# Reflow-controller-ESP32.net
KiCad netlist of a schematic drawn in EAGLE
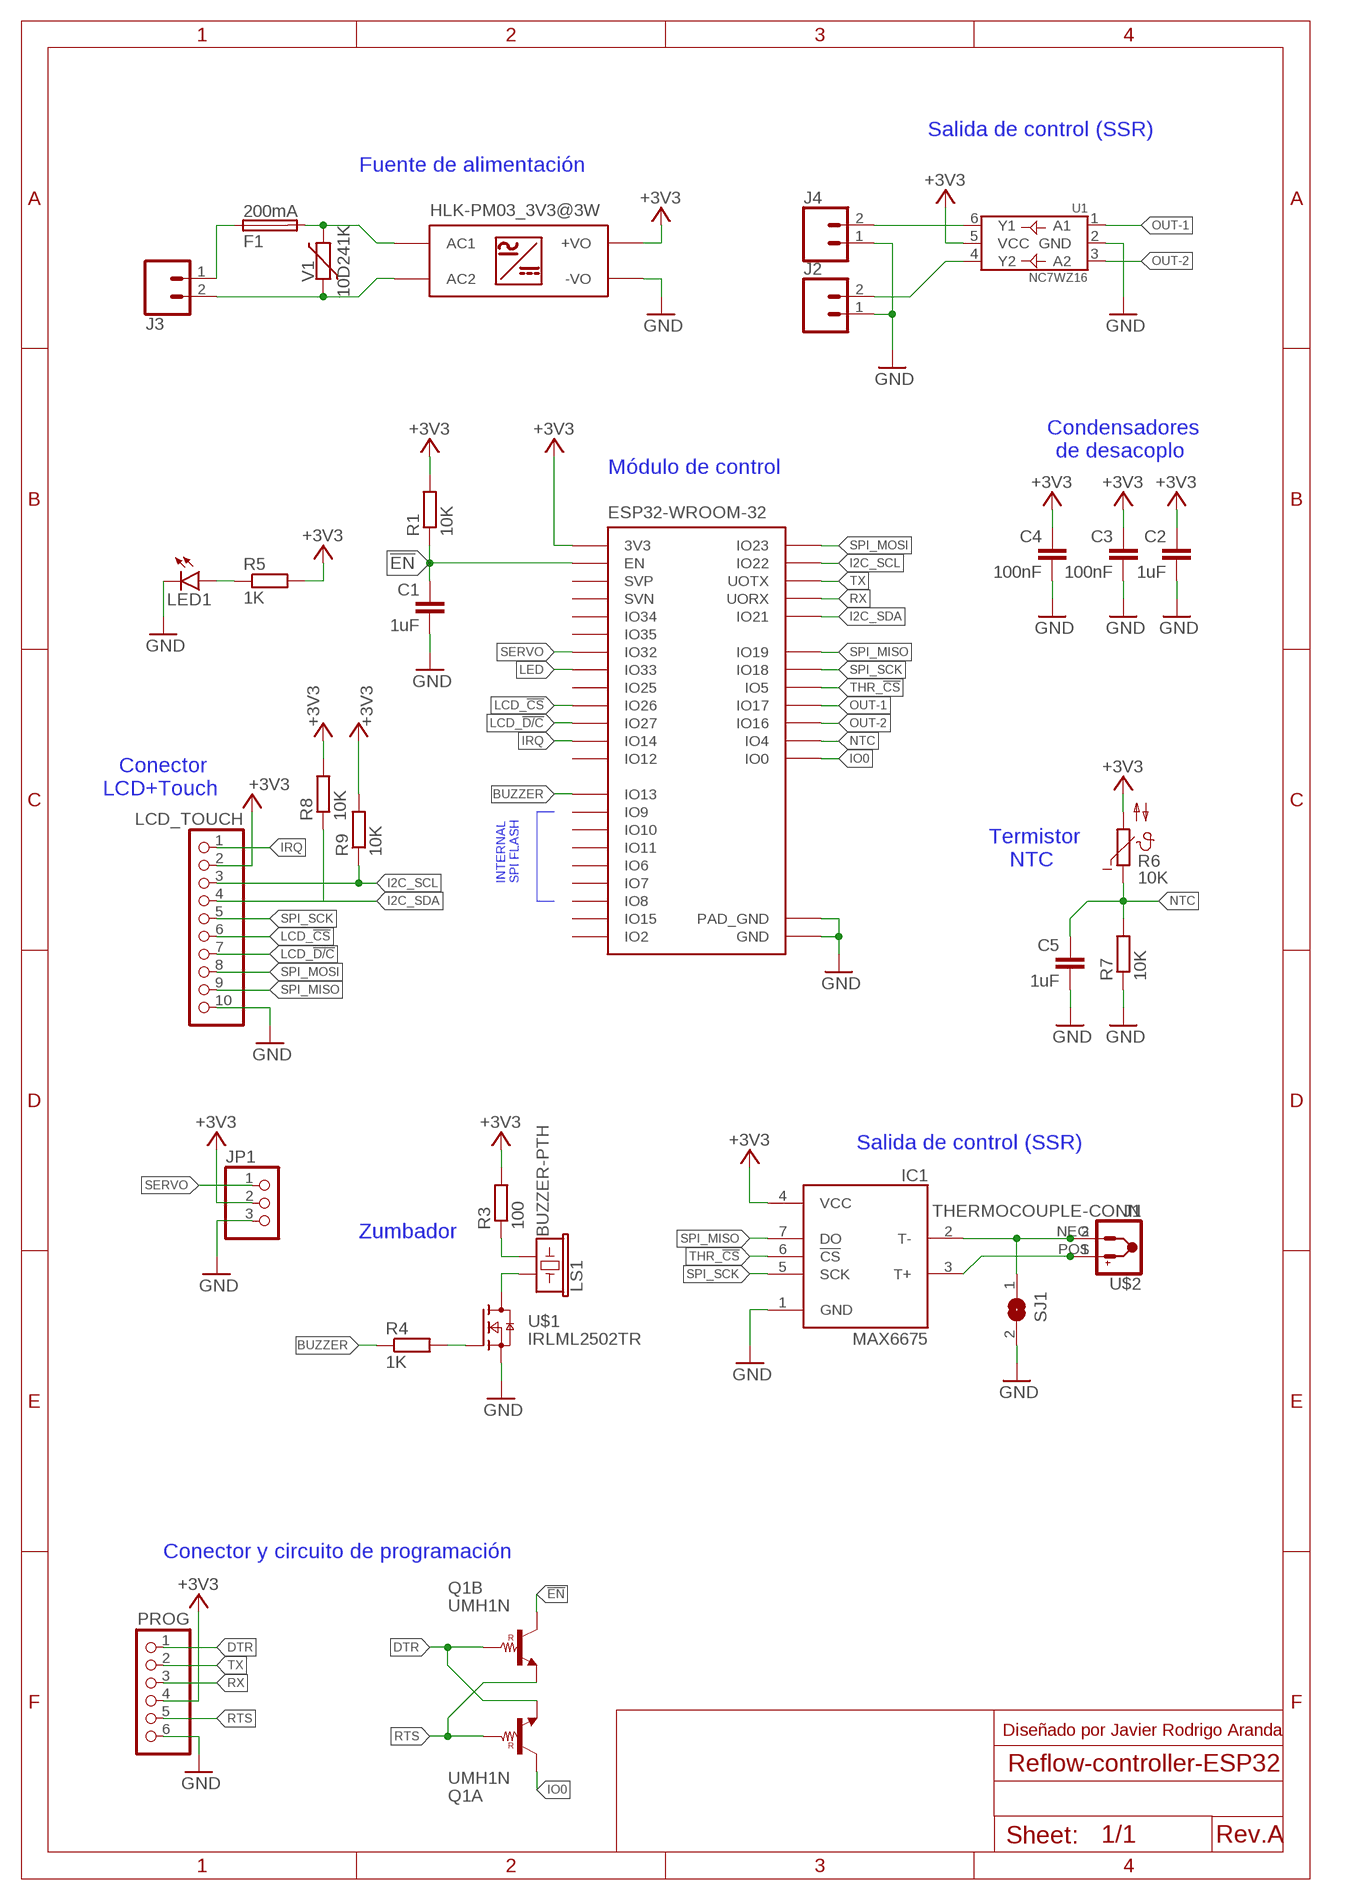
[diagram p0: schematic, sheet 1]

(export (version "E")
  (design (tool "Eeschema 10.0.6"))
  (components
    (comp (ref "C1")
      (value "1uF")
      (footprint "eagle-import:C0805")
      (libsource (lib "eagle-import") (part "C-EUC0805"))
    )
    (comp (ref "C2")
      (value "1uF")
      (footprint "eagle-import:C0805")
      (libsource (lib "eagle-import") (part "C-EUC0805"))
    )
    (comp (ref "C3")
      (value "100nF")
      (footprint "eagle-import:C0805")
      (libsource (lib "eagle-import") (part "C-EUC0805"))
    )
    (comp (ref "C4")
      (value "100nF")
      (footprint "eagle-import:C0805")
      (libsource (lib "eagle-import") (part "C-EUC0805"))
    )
    (comp (ref "C5")
      (value "1uF")
      (footprint "eagle-import:C0805")
      (libsource (lib "eagle-import") (part "C-EUC0805"))
    )
    (comp (ref "ESP32-WROOM-32")
      (value "ESP32")
      (footprint "eagle-import:ESP32-WROOM-32")
      (libsource (lib "eagle-import") (part "ESP32"))
    )
    (comp (ref "F1")
      (value "200mA")
      (footprint "eagle-import:SH22,5")
      (fields (field (name "MF") "SCHURTER") (field (name "MPN") "0031.8201"))
      (libsource (lib "eagle-import") (part "SH22,5"))
    )
    (comp (ref "HLK-PM03_3V3@3W")
      (value "HLK-PM0X")
      (footprint "eagle-import:HLK-PM0X")
      (libsource (lib "eagle-import") (part "HLK-PM0X"))
    )
    (comp (ref "IC1")
      (value "MAX6675")
      (footprint "eagle-import:SO08")
      (libsource (lib "eagle-import") (part "MAX6675"))
    )
    (comp (ref "J1")
      (value "HEADER_01X025MM-BIG")
      (footprint "eagle-import:SCREWTERMINAL-5MM-BIG-BLOCK")
      (libsource (lib "eagle-import") (part "HEADER_01X025MM-BIG"))
    )
    (comp (ref "J2")
      (value "HEADER_01X025MM-BIG")
      (footprint "eagle-import:SCREWTERMINAL-5MM-BIG-BLOCK")
      (libsource (lib "eagle-import") (part "HEADER_01X025MM-BIG"))
    )
    (comp (ref "J3")
      (value "HEADER_01X025MM-BIG")
      (footprint "eagle-import:SCREWTERMINAL-5MM-BIG-BLOCK")
      (libsource (lib "eagle-import") (part "HEADER_01X025MM-BIG"))
    )
    (comp (ref "J4")
      (value "HEADER_01X025MM-BIG")
      (footprint "eagle-import:SCREWTERMINAL-5MM-BIG-BLOCK")
      (libsource (lib "eagle-import") (part "HEADER_01X025MM-BIG"))
    )
    (comp (ref "JP1")
      (value "PINHD-1X3")
      (footprint "eagle-import:1X03")
      (libsource (lib "eagle-import") (part "PINHD-1X3"))
    )
    (comp (ref "LCD_TOUCH")
      (value "PINHD-1X10")
      (footprint "eagle-import:1X10")
      (libsource (lib "eagle-import") (part "PINHD-1X10"))
    )
    (comp (ref "LED1")
      (value "LEDSML1206")
      (footprint "eagle-import:SML1206")
      (libsource (lib "eagle-import") (part "LEDSML1206"))
    )
    (comp (ref "LS1")
      (value "BUZZER-PTH")
      (footprint "eagle-import:BUZZER-12MM")
      (libsource (lib "eagle-import") (part "BUZZER-PTH"))
    )
    (comp (ref "PROG")
      (value "PINHD-1X6")
      (footprint "eagle-import:1X06")
      (libsource (lib "eagle-import") (part "PINHD-1X6"))
    )
    (comp (ref "Q1")
      (value "UMH1N")
      (footprint "eagle-import:UMT6")
      (fields (field (name "MPN") "UMX1NTN"))
      (libsource (lib "eagle-import") (part "UMX1N"))
    )
    (comp (ref "R1")
      (value "10K")
      (footprint "eagle-import:R0805")
      (libsource (lib "eagle-import") (part "R-EU_R0805"))
    )
    (comp (ref "R3")
      (value "100")
      (footprint "eagle-import:R0805")
      (libsource (lib "eagle-import") (part "R-EU_R0805"))
    )
    (comp (ref "R4")
      (value "1K")
      (footprint "eagle-import:R0805")
      (libsource (lib "eagle-import") (part "R-EU_R0805"))
    )
    (comp (ref "R5")
      (value "1K")
      (footprint "eagle-import:R0805")
      (libsource (lib "eagle-import") (part "R-EU_R0805"))
    )
    (comp (ref "R6")
      (value "10K")
      (footprint "eagle-import:P642")
      (libsource (lib "eagle-import") (part "NTC642-6"))
    )
    (comp (ref "R7")
      (value "10K")
      (footprint "eagle-import:R0805")
      (libsource (lib "eagle-import") (part "R-EU_R0805"))
    )
    (comp (ref "R8")
      (value "10K")
      (footprint "eagle-import:R0805")
      (libsource (lib "eagle-import") (part "R-EU_R0805"))
    )
    (comp (ref "R9")
      (value "10K")
      (footprint "eagle-import:R0805")
      (libsource (lib "eagle-import") (part "R-EU_R0805"))
    )
    (comp (ref "SJ1") (value "SJ") (footprint "eagle-import:SJ") (libsource (lib "eagle-import") (part "SJ")))
    (comp (ref "U$1")
      (value "IRLML2502TR")
      (footprint "eagle-import:SOT23-3")
      (libsource (lib "eagle-import") (part "IRLML2502TR"))
    )
    (comp (ref "U$2")
      (value "THERMOCOUPLE-CONN")
      (footprint "eagle-import:THERMOCOUPLE-ONBOARD-CONN")
      (libsource (lib "eagle-import") (part "THERMOCOUPLE-CONN"))
    )
    (comp (ref "U1")
      (value "NC7WZ16")
      (footprint "eagle-import:SC-70-6")
      (libsource (lib "eagle-import") (part "NC7WZ16"))
    )
    (comp (ref "V1")
      (value "10D241K")
      (footprint "eagle-import:R-7,5")
      (libsource (lib "eagle-import") (part "VARISTOR-7,5"))
    )
  )
  (nets
    (net (code "1") (name "+3V3") (class "Default")
      (node (ref "C2") (pin "1") (pinfunction "1_1") (pintype "passive"))
      (node (ref "C3") (pin "1") (pinfunction "1_1") (pintype "passive"))
      (node (ref "C4") (pin "1") (pinfunction "1_1") (pintype "passive"))
      (node (ref "ESP32-WROOM-32") (pin "2") (pinfunction "3V3_2") (pintype "power_in"))
      (node (ref "HLK-PM03_3V3@3W") (pin "P$4") (pinfunction "+VO_P$4") (pintype "power_in"))
      (node (ref "IC1") (pin "4") (pinfunction "VCC_4") (pintype "power_in"))
      (node (ref "JP1") (pin "2") (pinfunction "2_2") (pintype "passive"))
      (node (ref "LCD_TOUCH") (pin "2") (pinfunction "2_2") (pintype "passive"))
      (node (ref "PROG") (pin "4") (pinfunction "4_4") (pintype "passive"))
      (node (ref "R1") (pin "2") (pinfunction "2_2") (pintype "passive"))
      (node (ref "R3") (pin "2") (pinfunction "2_2") (pintype "passive"))
      (node (ref "R5") (pin "2") (pinfunction "2_2") (pintype "passive"))
      (node (ref "R6") (pin "2") (pinfunction "2_2") (pintype "passive"))
      (node (ref "R8") (pin "2") (pinfunction "2_2") (pintype "passive"))
      (node (ref "R9") (pin "2") (pinfunction "2_2") (pintype "passive"))
      (node (ref "U1") (pin "5") (pinfunction "VCC_5") (pintype "power_in"))
    )
    (net (code "2") (name "/LCD_~{CS}") (class "Default")
      (node (ref "ESP32-WROOM-32") (pin "11") (pinfunction "IO26_11") (pintype "bidirectional"))
      (node (ref "LCD_TOUCH") (pin "6") (pinfunction "6_6") (pintype "passive"))
    )
    (net (code "3") (name "/LCD_~{D{slash}C}") (class "Default")
      (node (ref "ESP32-WROOM-32") (pin "12") (pinfunction "IO27_12") (pintype "bidirectional"))
      (node (ref "LCD_TOUCH") (pin "7") (pinfunction "7_7") (pintype "passive"))
    )
    (net (code "4") (name "/THR_~{CS}") (class "Default")
      (node (ref "ESP32-WROOM-32") (pin "29") (pinfunction "IO5_29") (pintype "bidirectional"))
      (node (ref "IC1") (pin "6") (pinfunction "~{CS}_6") (pintype "input"))
    )
    (net (code "5") (name "/~{EN}") (class "Default")
      (node (ref "C1") (pin "1") (pinfunction "1_1") (pintype "passive"))
      (node (ref "ESP32-WROOM-32") (pin "3") (pinfunction "EN_3") (pintype "bidirectional"))
      (node (ref "Q1") (pin "3") (pinfunction "C_3") (pintype "passive"))
      (node (ref "R1") (pin "1") (pinfunction "1_1") (pintype "passive"))
    )
    (net (code "6") (name "BUZZER") (class "Default")
      (node (ref "ESP32-WROOM-32") (pin "16") (pinfunction "IO13_16") (pintype "bidirectional"))
      (node (ref "R4") (pin "1") (pinfunction "1_1") (pintype "passive"))
    )
    (net (code "7") (name "DTR") (class "Default")
      (node (ref "PROG") (pin "1") (pinfunction "1_1") (pintype "passive"))
      (node (ref "Q1") (pin "1") (pinfunction "E_1") (pintype "passive"))
      (node (ref "Q1") (pin "5") (pinfunction "B_5") (pintype "passive"))
    )
    (net (code "8") (name "GND") (class "Default")
      (node (ref "C1") (pin "2") (pinfunction "2_2") (pintype "passive"))
      (node (ref "C2") (pin "2") (pinfunction "2_2") (pintype "passive"))
      (node (ref "C3") (pin "2") (pinfunction "2_2") (pintype "passive"))
      (node (ref "C4") (pin "2") (pinfunction "2_2") (pintype "passive"))
      (node (ref "C5") (pin "2") (pinfunction "2_2") (pintype "passive"))
      (node (ref "ESP32-WROOM-32") (pin "1") (pinfunction "GND_1") (pintype "power_in"))
      (node (ref "ESP32-WROOM-32") (pin "15") (pinfunction "GND_15") (pintype "power_in"))
      (node (ref "ESP32-WROOM-32") (pin "38") (pinfunction "GND_38") (pintype "power_in"))
      (node (ref "ESP32-WROOM-32") (pin "GND") (pinfunction "PAD_GND_GND") (pintype "power_in"))
      (node (ref "HLK-PM03_3V3@3W") (pin "P$3") (pinfunction "-VO_P$3") (pintype "power_in"))
      (node (ref "IC1") (pin "1") (pinfunction "GND_1") (pintype "power_in"))
      (node (ref "J2") (pin "1") (pinfunction "1_1") (pintype "passive"))
      (node (ref "J4") (pin "1") (pinfunction "1_1") (pintype "passive"))
      (node (ref "JP1") (pin "3") (pinfunction "3_3") (pintype "passive"))
      (node (ref "LCD_TOUCH") (pin "10") (pinfunction "10_10") (pintype "passive"))
      (node (ref "LED1") (pin "C") (pinfunction "C_C") (pintype "passive"))
      (node (ref "PROG") (pin "6") (pinfunction "6_6") (pintype "passive"))
      (node (ref "R7") (pin "1") (pinfunction "1_1") (pintype "passive"))
      (node (ref "SJ1") (pin "2") (pinfunction "2_2") (pintype "passive"))
      (node (ref "U$1") (pin "2") (pinfunction "S_2") (pintype "passive"))
      (node (ref "U1") (pin "2") (pinfunction "GND_2") (pintype "power_in"))
    )
    (net (code "9") (name "I2C_SCL") (class "Default")
      (node (ref "ESP32-WROOM-32") (pin "36") (pinfunction "IO22_36") (pintype "bidirectional"))
      (node (ref "LCD_TOUCH") (pin "3") (pinfunction "3_3") (pintype "passive"))
      (node (ref "R9") (pin "1") (pinfunction "1_1") (pintype "passive"))
    )
    (net (code "10") (name "I2C_SDA") (class "Default")
      (node (ref "ESP32-WROOM-32") (pin "33") (pinfunction "IO21_33") (pintype "bidirectional"))
      (node (ref "LCD_TOUCH") (pin "4") (pinfunction "4_4") (pintype "passive"))
      (node (ref "R8") (pin "1") (pinfunction "1_1") (pintype "passive"))
    )
    (net (code "11") (name "IO0") (class "Default")
      (node (ref "ESP32-WROOM-32") (pin "25") (pinfunction "IO0_25") (pintype "bidirectional"))
      (node (ref "Q1") (pin "6") (pinfunction "C_6") (pintype "passive"))
    )
    (net (code "12") (name "IRQ") (class "Default")
      (node (ref "ESP32-WROOM-32") (pin "13") (pinfunction "IO14_13") (pintype "bidirectional"))
      (node (ref "LCD_TOUCH") (pin "1") (pinfunction "1_1") (pintype "passive"))
    )
    (net (code "13") (name "LED") (class "Default")
      (node (ref "ESP32-WROOM-32") (pin "9") (pinfunction "IO33_9") (pintype "bidirectional"))
    )
    (net (code "14") (name "NTC") (class "Default")
      (node (ref "C5") (pin "1") (pinfunction "1_1") (pintype "passive"))
      (node (ref "ESP32-WROOM-32") (pin "26") (pinfunction "IO4_26") (pintype "bidirectional"))
      (node (ref "R6") (pin "1") (pinfunction "1_1") (pintype "passive"))
      (node (ref "R7") (pin "2") (pinfunction "2_2") (pintype "passive"))
    )
    (net (code "15") (name "Net-(F1-Pad1)") (class "Default")
      (node (ref "F1") (pin "1") (pinfunction "1_1") (pintype "passive"))
      (node (ref "J3") (pin "1") (pinfunction "1_1") (pintype "passive"))
    )
    (net (code "16") (name "Net-(HLK-PM03_3V3@3W-AC1)") (class "Default")
      (node (ref "F1") (pin "2") (pinfunction "2_2") (pintype "passive"))
      (node (ref "HLK-PM03_3V3@3W") (pin "P$1") (pinfunction "AC1_P$1") (pintype "power_in"))
      (node (ref "V1") (pin "2") (pinfunction "2_2") (pintype "passive"))
    )
    (net (code "17") (name "Net-(HLK-PM03_3V3@3W-AC2)") (class "Default")
      (node (ref "HLK-PM03_3V3@3W") (pin "P$2") (pinfunction "AC2_P$2") (pintype "power_in"))
      (node (ref "J3") (pin "2") (pinfunction "2_2") (pintype "passive"))
      (node (ref "V1") (pin "1") (pinfunction "1_1") (pintype "passive"))
    )
    (net (code "18") (name "Net-(IC1-T+)") (class "Default")
      (node (ref "IC1") (pin "3") (pinfunction "T+_3") (pintype "input"))
      (node (ref "J1") (pin "1") (pinfunction "1_1") (pintype "passive"))
      (node (ref "U$2") (pin "POS") (pinfunction "POS_POS") (pintype "passive"))
    )
    (net (code "19") (name "Net-(IC1-T-)") (class "Default")
      (node (ref "IC1") (pin "2") (pinfunction "T-_2") (pintype "input"))
      (node (ref "J1") (pin "2") (pinfunction "2_2") (pintype "passive"))
      (node (ref "SJ1") (pin "1") (pinfunction "1_1") (pintype "passive"))
      (node (ref "U$2") (pin "NEG") (pinfunction "NEG_NEG") (pintype "passive"))
    )
    (net (code "20") (name "Net-(LED1-PadA)") (class "Default")
      (node (ref "LED1") (pin "A") (pinfunction "A_A") (pintype "passive"))
      (node (ref "R5") (pin "1") (pinfunction "1_1") (pintype "passive"))
    )
    (net (code "21") (name "Net-(LS1-1)") (class "Default")
      (node (ref "LS1") (pin "+") (pinfunction "1_+") (pintype "passive"))
      (node (ref "U$1") (pin "3") (pinfunction "D_3") (pintype "passive"))
    )
    (net (code "22") (name "Net-(LS1-2)") (class "Default")
      (node (ref "LS1") (pin "-") (pinfunction "2_-") (pintype "passive"))
      (node (ref "R3") (pin "1") (pinfunction "1_1") (pintype "passive"))
    )
    (net (code "23") (name "Net-(U$1-G)") (class "Default")
      (node (ref "R4") (pin "2") (pinfunction "2_2") (pintype "passive"))
      (node (ref "U$1") (pin "1") (pinfunction "G_1") (pintype "passive"))
    )
    (net (code "24") (name "Net-(U1-Y1)") (class "Default")
      (node (ref "J4") (pin "2") (pinfunction "2_2") (pintype "passive"))
      (node (ref "U1") (pin "6") (pinfunction "Y1_6") (pintype "bidirectional"))
    )
    (net (code "25") (name "Net-(U1-Y2)") (class "Default")
      (node (ref "J2") (pin "2") (pinfunction "2_2") (pintype "passive"))
      (node (ref "U1") (pin "4") (pinfunction "Y2_4") (pintype "bidirectional"))
    )
    (net (code "26") (name "OUT-1") (class "Default")
      (node (ref "ESP32-WROOM-32") (pin "28") (pinfunction "IO17_28") (pintype "bidirectional"))
      (node (ref "U1") (pin "1") (pinfunction "A1_1") (pintype "bidirectional"))
    )
    (net (code "27") (name "OUT-2") (class "Default")
      (node (ref "ESP32-WROOM-32") (pin "27") (pinfunction "IO16_27") (pintype "bidirectional"))
      (node (ref "U1") (pin "3") (pinfunction "A2_3") (pintype "bidirectional"))
    )
    (net (code "28") (name "RTS") (class "Default")
      (node (ref "PROG") (pin "5") (pinfunction "5_5") (pintype "passive"))
      (node (ref "Q1") (pin "2") (pinfunction "B_2") (pintype "passive"))
      (node (ref "Q1") (pin "4") (pinfunction "E_4") (pintype "passive"))
    )
    (net (code "29") (name "RX") (class "Default")
      (node (ref "ESP32-WROOM-32") (pin "34") (pinfunction "UORX_34") (pintype "bidirectional"))
      (node (ref "PROG") (pin "3") (pinfunction "3_3") (pintype "passive"))
    )
    (net (code "30") (name "SERVO") (class "Default")
      (node (ref "ESP32-WROOM-32") (pin "8") (pinfunction "IO32_8") (pintype "bidirectional"))
      (node (ref "JP1") (pin "1") (pinfunction "1_1") (pintype "passive"))
    )
    (net (code "31") (name "SPI_MISO") (class "Default")
      (node (ref "ESP32-WROOM-32") (pin "31") (pinfunction "IO19_31") (pintype "bidirectional"))
      (node (ref "IC1") (pin "7") (pinfunction "DO_7") (pintype "output"))
      (node (ref "LCD_TOUCH") (pin "9") (pinfunction "9_9") (pintype "passive"))
    )
    (net (code "32") (name "SPI_MOSI") (class "Default")
      (node (ref "ESP32-WROOM-32") (pin "37") (pinfunction "IO23_37") (pintype "bidirectional"))
      (node (ref "LCD_TOUCH") (pin "8") (pinfunction "8_8") (pintype "passive"))
    )
    (net (code "33") (name "SPI_SCK") (class "Default")
      (node (ref "ESP32-WROOM-32") (pin "30") (pinfunction "IO18_30") (pintype "bidirectional"))
      (node (ref "IC1") (pin "5") (pinfunction "SCK_5") (pintype "input"))
      (node (ref "LCD_TOUCH") (pin "5") (pinfunction "5_5") (pintype "passive"))
    )
    (net (code "34") (name "TX") (class "Default")
      (node (ref "ESP32-WROOM-32") (pin "35") (pinfunction "UOTX_35") (pintype "bidirectional"))
      (node (ref "PROG") (pin "2") (pinfunction "2_2") (pintype "passive"))
    )
    (net (code "35") (name "unconnected-(ESP32-WROOM-32-IO2-Pad24)") (class "Default")
      (node (ref "ESP32-WROOM-32") (pin "24") (pinfunction "IO2_24") (pintype "bidirectional"))
    )
    (net (code "36") (name "unconnected-(ESP32-WROOM-32-IO6-Pad20)") (class "Default")
      (node (ref "ESP32-WROOM-32") (pin "20") (pinfunction "IO6_20") (pintype "bidirectional"))
    )
    (net (code "37") (name "unconnected-(ESP32-WROOM-32-IO7-Pad21)") (class "Default")
      (node (ref "ESP32-WROOM-32") (pin "21") (pinfunction "IO7_21") (pintype "bidirectional"))
    )
    (net (code "38") (name "unconnected-(ESP32-WROOM-32-IO8-Pad22)") (class "Default")
      (node (ref "ESP32-WROOM-32") (pin "22") (pinfunction "IO8_22") (pintype "bidirectional"))
    )
    (net (code "39") (name "unconnected-(ESP32-WROOM-32-IO9-Pad17)") (class "Default")
      (node (ref "ESP32-WROOM-32") (pin "17") (pinfunction "IO9_17") (pintype "bidirectional"))
    )
    (net (code "40") (name "unconnected-(ESP32-WROOM-32-IO10-Pad18)") (class "Default")
      (node (ref "ESP32-WROOM-32") (pin "18") (pinfunction "IO10_18") (pintype "bidirectional"))
    )
    (net (code "41") (name "unconnected-(ESP32-WROOM-32-IO11-Pad19)") (class "Default")
      (node (ref "ESP32-WROOM-32") (pin "19") (pinfunction "IO11_19") (pintype "bidirectional"))
    )
    (net (code "42") (name "unconnected-(ESP32-WROOM-32-IO12-Pad14)") (class "Default")
      (node (ref "ESP32-WROOM-32") (pin "14") (pinfunction "IO12_14") (pintype "bidirectional"))
    )
    (net (code "43") (name "unconnected-(ESP32-WROOM-32-IO15-Pad23)") (class "Default")
      (node (ref "ESP32-WROOM-32") (pin "23") (pinfunction "IO15_23") (pintype "bidirectional"))
    )
    (net (code "44") (name "unconnected-(ESP32-WROOM-32-IO25-Pad10)") (class "Default")
      (node (ref "ESP32-WROOM-32") (pin "10") (pinfunction "IO25_10") (pintype "bidirectional"))
    )
    (net (code "45") (name "unconnected-(ESP32-WROOM-32-IO34-Pad6)") (class "Default")
      (node (ref "ESP32-WROOM-32") (pin "6") (pinfunction "IO34_6") (pintype "bidirectional"))
    )
    (net (code "46") (name "unconnected-(ESP32-WROOM-32-IO35-Pad7)") (class "Default")
      (node (ref "ESP32-WROOM-32") (pin "7") (pinfunction "IO35_7") (pintype "bidirectional"))
    )
    (net (code "47") (name "unconnected-(ESP32-WROOM-32-SVN-Pad5)") (class "Default")
      (node (ref "ESP32-WROOM-32") (pin "5") (pinfunction "SVN_5") (pintype "bidirectional"))
    )
    (net (code "48") (name "unconnected-(ESP32-WROOM-32-SVP-Pad4)") (class "Default")
      (node (ref "ESP32-WROOM-32") (pin "4") (pinfunction "SVP_4") (pintype "bidirectional"))
    )
  )
)
